# Gate_drivers.net
KiCad netlist of a schematic drawn in Altium Designer
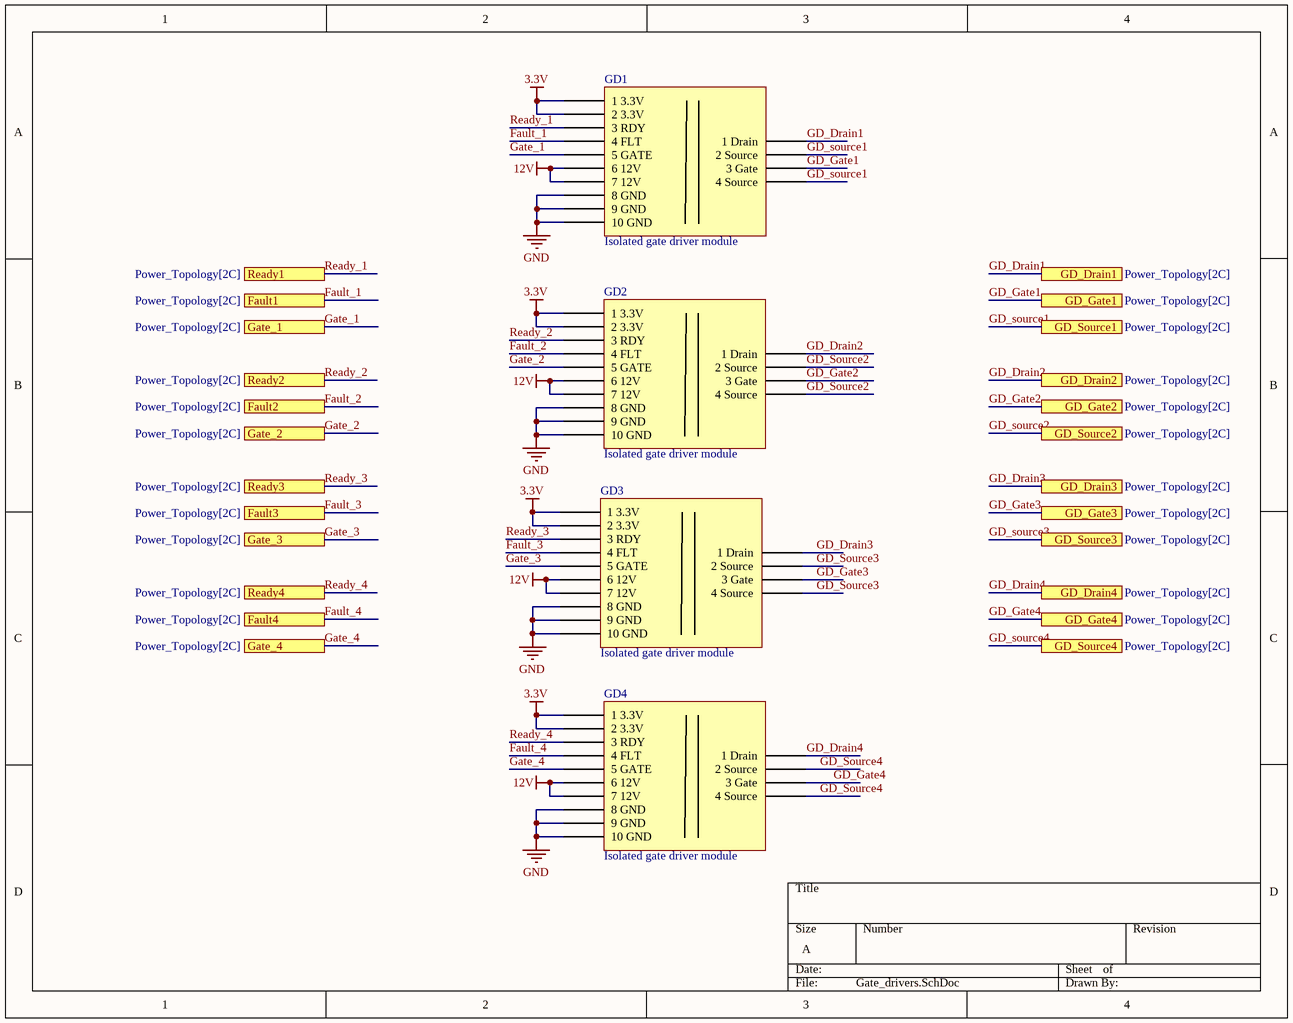
[diagram p0: Gate_drivers.SchDoc]

(export (version "E")
  (design (tool "Eeschema 10.0.6"))
  (components
    (comp (ref "GD1")
      (value "Isolated gate driver module")
      (footprint "CON_ISOLATED_GATE_DRIVER_MODULE")
      (description "10 + 4 Position Receptacle Connector 0.079\" (2.00mm) Through Hole Gold")
      (fields (field (name "MF") "Samtec Inc.") (field (name "CREATED") "2021_07_07_DArancibia"))
      (libsource (lib "H-Bridge 3-Leg - Lib") (part "Con_Isolated_gate_driver_module"))
    )
    (comp (ref "GD2")
      (value "Isolated gate driver module")
      (footprint "CON_ISOLATED_GATE_DRIVER_MODULE")
      (description "10 + 4 Position Receptacle Connector 0.079\" (2.00mm) Through Hole Gold")
      (fields (field (name "MF") "Samtec Inc.") (field (name "CREATED") "2021_07_07_DArancibia"))
      (libsource (lib "H-Bridge 3-Leg - Lib") (part "Con_Isolated_gate_driver_module"))
    )
    (comp (ref "GD3")
      (value "Isolated gate driver module")
      (footprint "CON_ISOLATED_GATE_DRIVER_MODULE")
      (description "10 + 4 Position Receptacle Connector 0.079\" (2.00mm) Through Hole Gold")
      (fields (field (name "MF") "Samtec Inc.") (field (name "CREATED") "2021_07_07_DArancibia"))
      (libsource (lib "H-Bridge 3-Leg - Lib") (part "Con_Isolated_gate_driver_module"))
    )
    (comp (ref "GD4")
      (value "Isolated gate driver module")
      (footprint "CON_ISOLATED_GATE_DRIVER_MODULE")
      (description "10 + 4 Position Receptacle Connector 0.079\" (2.00mm) Through Hole Gold")
      (fields (field (name "MF") "Samtec Inc.") (field (name "CREATED") "2021_07_07_DArancibia"))
      (libsource (lib "H-Bridge 3-Leg - Lib") (part "Con_Isolated_gate_driver_module"))
    )
  )
  (nets
    (net (code "1") (name "/Fault_1") (class "Default")
      (node (ref "GD1") (pin "4") (pinfunction "4_FLT_4") (pintype "passive"))
    )
    (net (code "2") (name "/Fault_2") (class "Default")
      (node (ref "GD2") (pin "4") (pinfunction "4_FLT_4") (pintype "passive"))
    )
    (net (code "3") (name "/Fault_3") (class "Default")
      (node (ref "GD3") (pin "4") (pinfunction "4_FLT_4") (pintype "passive"))
    )
    (net (code "4") (name "/Fault_4") (class "Default")
      (node (ref "GD4") (pin "4") (pinfunction "4_FLT_4") (pintype "passive"))
    )
    (net (code "5") (name "/GD_Drain1") (class "Default")
      (node (ref "GD1") (pin "11") (pinfunction "1_Drain_11") (pintype "passive"))
    )
    (net (code "6") (name "/GD_Drain2") (class "Default")
      (node (ref "GD2") (pin "11") (pinfunction "1_Drain_11") (pintype "passive"))
    )
    (net (code "7") (name "/GD_Drain3") (class "Default")
      (node (ref "GD3") (pin "11") (pinfunction "1_Drain_11") (pintype "passive"))
    )
    (net (code "8") (name "/GD_Drain4") (class "Default")
      (node (ref "GD4") (pin "11") (pinfunction "1_Drain_11") (pintype "passive"))
    )
    (net (code "9") (name "/GD_Gate1") (class "Default")
      (node (ref "GD1") (pin "13") (pinfunction "3_Gate_13") (pintype "passive"))
    )
    (net (code "10") (name "/GD_Gate2") (class "Default")
      (node (ref "GD2") (pin "13") (pinfunction "3_Gate_13") (pintype "passive"))
    )
    (net (code "11") (name "/GD_Gate3") (class "Default")
      (node (ref "GD3") (pin "13") (pinfunction "3_Gate_13") (pintype "passive"))
    )
    (net (code "12") (name "/GD_Gate4") (class "Default")
      (node (ref "GD4") (pin "13") (pinfunction "3_Gate_13") (pintype "passive"))
    )
    (net (code "13") (name "/GD_Source2") (class "Default")
      (node (ref "GD2") (pin "12") (pinfunction "2_Source_12") (pintype "passive"))
      (node (ref "GD2") (pin "14") (pinfunction "4_Source_14") (pintype "passive"))
    )
    (net (code "14") (name "/GD_Source3") (class "Default")
      (node (ref "GD3") (pin "12") (pinfunction "2_Source_12") (pintype "passive"))
      (node (ref "GD3") (pin "14") (pinfunction "4_Source_14") (pintype "passive"))
    )
    (net (code "15") (name "/GD_Source4") (class "Default")
      (node (ref "GD4") (pin "12") (pinfunction "2_Source_12") (pintype "passive"))
      (node (ref "GD4") (pin "14") (pinfunction "4_Source_14") (pintype "passive"))
    )
    (net (code "16") (name "/GD_source1") (class "Default")
      (node (ref "GD1") (pin "12") (pinfunction "2_Source_12") (pintype "passive"))
      (node (ref "GD1") (pin "14") (pinfunction "4_Source_14") (pintype "passive"))
    )
    (net (code "17") (name "/Gate_1") (class "Default")
      (node (ref "GD1") (pin "5") (pinfunction "5_GATE_5") (pintype "passive"))
    )
    (net (code "18") (name "/Gate_2") (class "Default")
      (node (ref "GD2") (pin "5") (pinfunction "5_GATE_5") (pintype "passive"))
    )
    (net (code "19") (name "/Gate_3") (class "Default")
      (node (ref "GD3") (pin "5") (pinfunction "5_GATE_5") (pintype "passive"))
    )
    (net (code "20") (name "/Gate_4") (class "Default")
      (node (ref "GD4") (pin "5") (pinfunction "5_GATE_5") (pintype "passive"))
    )
    (net (code "21") (name "/Ready_1") (class "Default")
      (node (ref "GD1") (pin "3") (pinfunction "3_RDY_3") (pintype "passive"))
    )
    (net (code "22") (name "/Ready_2") (class "Default")
      (node (ref "GD2") (pin "3") (pinfunction "3_RDY_3") (pintype "passive"))
    )
    (net (code "23") (name "/Ready_3") (class "Default")
      (node (ref "GD3") (pin "3") (pinfunction "3_RDY_3") (pintype "passive"))
    )
    (net (code "24") (name "/Ready_4") (class "Default")
      (node (ref "GD4") (pin "3") (pinfunction "3_RDY_3") (pintype "passive"))
    )
    (net (code "25") (name "3.3V") (class "Default")
      (node (ref "GD1") (pin "1") (pinfunction "1_3.3V_1") (pintype "passive"))
      (node (ref "GD1") (pin "2") (pinfunction "2_3.3V_2") (pintype "passive"))
      (node (ref "GD2") (pin "1") (pinfunction "1_3.3V_1") (pintype "passive"))
      (node (ref "GD2") (pin "2") (pinfunction "2_3.3V_2") (pintype "passive"))
      (node (ref "GD3") (pin "1") (pinfunction "1_3.3V_1") (pintype "passive"))
      (node (ref "GD3") (pin "2") (pinfunction "2_3.3V_2") (pintype "passive"))
      (node (ref "GD4") (pin "1") (pinfunction "1_3.3V_1") (pintype "passive"))
      (node (ref "GD4") (pin "2") (pinfunction "2_3.3V_2") (pintype "passive"))
    )
    (net (code "26") (name "12V") (class "Default")
      (node (ref "GD1") (pin "6") (pinfunction "6_12V_6") (pintype "passive"))
      (node (ref "GD1") (pin "7") (pinfunction "7_12V_7") (pintype "passive"))
      (node (ref "GD2") (pin "6") (pinfunction "6_12V_6") (pintype "passive"))
      (node (ref "GD2") (pin "7") (pinfunction "7_12V_7") (pintype "passive"))
      (node (ref "GD3") (pin "6") (pinfunction "6_12V_6") (pintype "passive"))
      (node (ref "GD3") (pin "7") (pinfunction "7_12V_7") (pintype "passive"))
      (node (ref "GD4") (pin "6") (pinfunction "6_12V_6") (pintype "passive"))
      (node (ref "GD4") (pin "7") (pinfunction "7_12V_7") (pintype "passive"))
    )
    (net (code "27") (name "GND") (class "Default")
      (node (ref "GD1") (pin "10") (pinfunction "10_GND_10") (pintype "passive"))
      (node (ref "GD1") (pin "8") (pinfunction "8_GND_8") (pintype "passive"))
      (node (ref "GD1") (pin "9") (pinfunction "9_GND_9") (pintype "passive"))
      (node (ref "GD2") (pin "10") (pinfunction "10_GND_10") (pintype "passive"))
      (node (ref "GD2") (pin "8") (pinfunction "8_GND_8") (pintype "passive"))
      (node (ref "GD2") (pin "9") (pinfunction "9_GND_9") (pintype "passive"))
      (node (ref "GD3") (pin "10") (pinfunction "10_GND_10") (pintype "passive"))
      (node (ref "GD3") (pin "8") (pinfunction "8_GND_8") (pintype "passive"))
      (node (ref "GD3") (pin "9") (pinfunction "9_GND_9") (pintype "passive"))
      (node (ref "GD4") (pin "10") (pinfunction "10_GND_10") (pintype "passive"))
      (node (ref "GD4") (pin "8") (pinfunction "8_GND_8") (pintype "passive"))
      (node (ref "GD4") (pin "9") (pinfunction "9_GND_9") (pintype "passive"))
    )
  )
)
